# Micro_Conection.net
KiCad netlist of a schematic drawn in Altium Designer
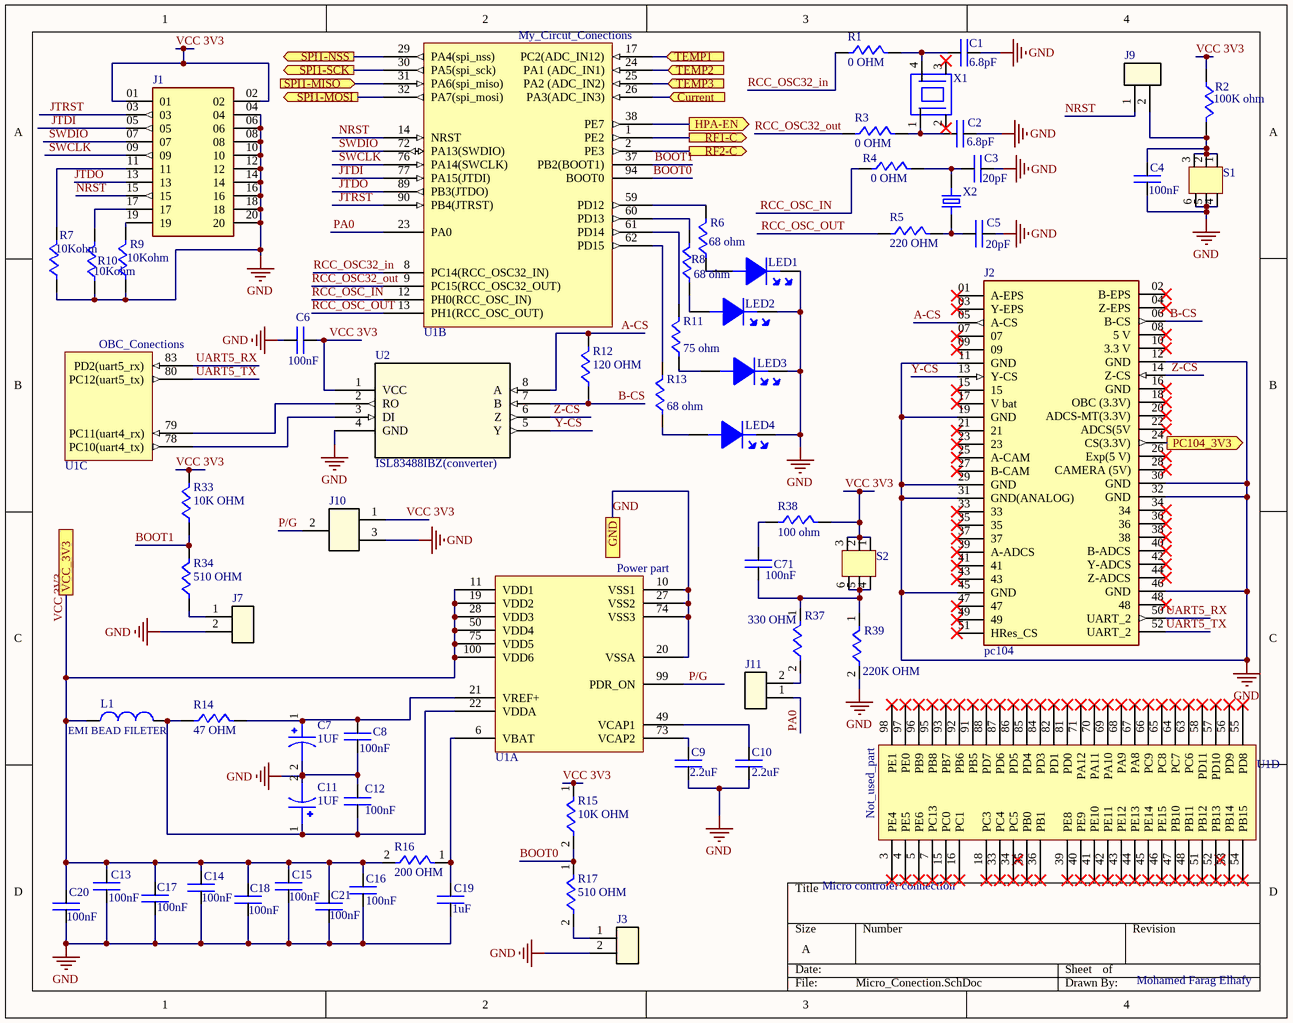
[diagram p0: Micro_Conection.SchDoc]

(export (version "E")
  (design (tool "Eeschema 10.0.6"))
  (components
    (comp (ref "C1")
      (value "CAP CER 6.8PF 100V NPO 0805")
      (footprint "0805 C")
      (description "6.8pF ±0.25pF 250V Ceramic Capacitor C0G, NP0 0805 (2012 Metric)")
      (fields
        (field (name "MANUFACTURER") "Yageo")
        (field (name "MANUFACTURER PART NUMBER") "CC0805CRNPO0BN6R8")
        (field (name "CAPACITANCE") "6.8pF")
      )
      (libsource (lib "comm sub") (part "C_6.8pF"))
    )
    (comp (ref "C2")
      (value "CAP CER 6.8PF 100V NPO 0805")
      (footprint "0805 C")
      (description "6.8pF ±0.25pF 250V Ceramic Capacitor C0G, NP0 0805 (2012 Metric)")
      (fields
        (field (name "MANUFACTURER") "Yageo")
        (field (name "MANUFACTURER PART NUMBER") "CC0805CRNPO0BN6R8")
        (field (name "CAPACITANCE") "6.8pF")
      )
      (libsource (lib "comm sub") (part "C_6.8pF"))
    )
    (comp (ref "C3")
      (value "CAP CER 20PF 25V NP0 0603")
      (footprint "0805 C")
      (description "20pF ±1% 25V Ceramic Capacitor C0G, NP0 0603 (1608 Metric)")
      (fields
        (field (name "MANUFACTURER") "Yageo")
        (field (name "MANUFACTURER PART NUMBER") "CC0805CRNPO0BN6R8")
        (field (name "CAPACITANCE") "20pF")
      )
      (libsource (lib "comm sub") (part "C_20pF"))
    )
    (comp (ref "C4")
      (value "CAP CER 0.1UF 10V 0805")
      (footprint "0805 C")
      (description "0.1µF ±10% 16V Ceramic Capacitor X7R 0805 (2012 Metric)")
      (fields
        (field (name "MANUFACTURER") "Johanson")
        (field (name "MANUFACTURER PART NUMBER") "160R15W104KV4T")
        (field (name "CAPACITANCE") "100nF")
      )
      (libsource (lib "comm sub") (part "C_100nF"))
    )
    (comp (ref "C5")
      (value "CAP CER 20PF 25V NP0 0603")
      (footprint "0805 C")
      (description "20pF ±1% 25V Ceramic Capacitor C0G, NP0 0603 (1608 Metric)")
      (fields
        (field (name "MANUFACTURER") "Yageo")
        (field (name "MANUFACTURER PART NUMBER") "CC0805CRNPO0BN6R8")
        (field (name "CAPACITANCE") "20pF")
      )
      (libsource (lib "comm sub") (part "C_20pF"))
    )
    (comp (ref "C6")
      (value "CAP CER 0.1UF 10V 0805")
      (footprint "0805 C")
      (description "0.1µF ±10% 16V Ceramic Capacitor X7R 0805 (2012 Metric)")
      (fields
        (field (name "MANUFACTURER") "Johanson")
        (field (name "MANUFACTURER PART NUMBER") "160R15W104KV4T")
        (field (name "CAPACITANCE") "100nF")
      )
      (libsource (lib "comm sub") (part "C_100nF"))
    )
    (comp (ref "C7")
      (value "1UF")
      (footprint "1206 C")
      (description "1µF Molded Tantalum Capacitors 16V 1206 (3216 Metric) 11Ohm")
      (libsource (lib "") (part "C_1uF 1206_1"))
    )
    (comp (ref "C8")
      (value "CAP CER 0.1UF 10V 0805")
      (footprint "0805 C")
      (description "0.1µF ±10% 16V Ceramic Capacitor X7R 0805 (2012 Metric)")
      (fields
        (field (name "MANUFACTURER") "Johanson")
        (field (name "MANUFACTURER PART NUMBER") "160R15W104KV4T")
        (field (name "CAPACITANCE") "100nF")
      )
      (libsource (lib "comm sub") (part "C_100nF"))
    )
    (comp (ref "C9")
      (value "CAP CER 2.2UF 25V X7R 0805")
      (footprint "0805 C")
      (description "2.2µF ±10% 25V Ceramic Capacitor X7R 0805 (2012 Metric)")
      (fields
        (field (name "MANUFACTURER") "Murata")
        (field (name "MANUFACTURER PART NUMBER") "GRM21BR71E225KE11L")
        (field (name "CAPACITANCE") "2.2uF")
      )
      (libsource (lib "comm sub") (part "C_2.2uF"))
    )
    (comp (ref "C10")
      (value "CAP CER 2.2UF 25V X7R 0805")
      (footprint "0805 C")
      (description "2.2µF ±10% 25V Ceramic Capacitor X7R 0805 (2012 Metric)")
      (fields
        (field (name "MANUFACTURER") "Murata")
        (field (name "MANUFACTURER PART NUMBER") "GRM21BR71E225KE11L")
        (field (name "CAPACITANCE") "2.2uF")
      )
      (libsource (lib "comm sub") (part "C_2.2uF"))
    )
    (comp (ref "C11")
      (value "1UF")
      (footprint "1206 C")
      (description "1µF Molded Tantalum Capacitors 16V 1206 (3216 Metric) 11Ohm")
      (libsource (lib "comm sub") (part "C_1uF 1206"))
    )
    (comp (ref "C12")
      (value "CAP CER 0.1UF 10V 0805")
      (footprint "0805 C")
      (description "0.1µF ±10% 16V Ceramic Capacitor X7R 0805 (2012 Metric)")
      (fields
        (field (name "MANUFACTURER") "Johanson")
        (field (name "MANUFACTURER PART NUMBER") "160R15W104KV4T")
        (field (name "CAPACITANCE") "100nF")
      )
      (libsource (lib "comm sub") (part "C_100nF"))
    )
    (comp (ref "C13")
      (value "CAP CER 0.1UF 10V 0805")
      (footprint "0805 C")
      (description "0.1µF ±10% 16V Ceramic Capacitor X7R 0805 (2012 Metric)")
      (fields
        (field (name "MANUFACTURER") "Johanson")
        (field (name "MANUFACTURER PART NUMBER") "160R15W104KV4T")
        (field (name "CAPACITANCE") "100nF")
      )
      (libsource (lib "comm sub") (part "C_100nF"))
    )
    (comp (ref "C14")
      (value "CAP CER 0.1UF 10V 0805")
      (footprint "0805 C")
      (description "0.1µF ±10% 16V Ceramic Capacitor X7R 0805 (2012 Metric)")
      (fields
        (field (name "MANUFACTURER") "Johanson")
        (field (name "MANUFACTURER PART NUMBER") "160R15W104KV4T")
        (field (name "CAPACITANCE") "100nF")
      )
      (libsource (lib "comm sub") (part "C_100nF"))
    )
    (comp (ref "C15")
      (value "CAP CER 0.1UF 10V 0805")
      (footprint "0805 C")
      (description "0.1µF ±10% 16V Ceramic Capacitor X7R 0805 (2012 Metric)")
      (fields
        (field (name "MANUFACTURER") "Johanson")
        (field (name "MANUFACTURER PART NUMBER") "160R15W104KV4T")
        (field (name "CAPACITANCE") "100nF")
      )
      (libsource (lib "comm sub") (part "C_100nF"))
    )
    (comp (ref "C16")
      (value "CAP CER 0.1UF 10V 0805")
      (footprint "0805 C")
      (description "0.1µF ±10% 16V Ceramic Capacitor X7R 0805 (2012 Metric)")
      (fields
        (field (name "MANUFACTURER") "Johanson")
        (field (name "MANUFACTURER PART NUMBER") "160R15W104KV4T")
        (field (name "CAPACITANCE") "100nF")
      )
      (libsource (lib "comm sub") (part "C_100nF"))
    )
    (comp (ref "C17")
      (value "CAP CER 0.1UF 10V 0805")
      (footprint "0805 C")
      (description "0.1µF ±10% 16V Ceramic Capacitor X7R 0805 (2012 Metric)")
      (fields
        (field (name "MANUFACTURER") "Johanson")
        (field (name "MANUFACTURER PART NUMBER") "160R15W104KV4T")
        (field (name "CAPACITANCE") "100nF")
      )
      (libsource (lib "comm sub") (part "C_100nF"))
    )
    (comp (ref "C18")
      (value "CAP CER 0.1UF 10V 0805")
      (footprint "0805 C")
      (description "0.1µF ±10% 16V Ceramic Capacitor X7R 0805 (2012 Metric)")
      (fields
        (field (name "MANUFACTURER") "Johanson")
        (field (name "MANUFACTURER PART NUMBER") "160R15W104KV4T")
        (field (name "CAPACITANCE") "100nF")
      )
      (libsource (lib "comm sub") (part "C_100nF"))
    )
    (comp (ref "C19")
      (value "CAP CER 1UF 16V X7R 0805")
      (footprint "0805 C")
      (description "1µF ±5% 16V Ceramic Capacitor X7R 0805 (2012 Metric)")
      (fields
        (field (name "MANUFACTURER") "Murata")
        (field (name "MANUFACTURER PART NUMBER") "GRM219R61H105KA73D")
        (field (name "CAPACITANCE") "1uF")
      )
      (libsource (lib "comm sub") (part "C_1uF"))
    )
    (comp (ref "C20")
      (value "CAP CER 0.1UF 10V 0805")
      (footprint "0805 C")
      (description "0.1µF ±10% 16V Ceramic Capacitor X7R 0805 (2012 Metric)")
      (fields
        (field (name "MANUFACTURER") "Johanson")
        (field (name "MANUFACTURER PART NUMBER") "160R15W104KV4T")
        (field (name "CAPACITANCE") "100nF")
      )
      (libsource (lib "comm sub") (part "C_100nF"))
    )
    (comp (ref "C21")
      (value "CAP CER 0.1UF 10V 0805")
      (footprint "0805 C")
      (description "0.1µF ±10% 16V Ceramic Capacitor X7R 0805 (2012 Metric)")
      (fields
        (field (name "MANUFACTURER") "Johanson")
        (field (name "MANUFACTURER PART NUMBER") "160R15W104KV4T")
        (field (name "CAPACITANCE") "100nF")
      )
      (libsource (lib "comm sub") (part "C_100nF"))
    )
    (comp (ref "C71")
      (value "CAP CER 0.1UF 10V 0805")
      (footprint "0805 C")
      (description "0.1µF ±10% 16V Ceramic Capacitor X7R 0805 (2012 Metric)")
      (fields
        (field (name "MANUFACTURER") "Johanson")
        (field (name "MANUFACTURER PART NUMBER") "160R15W104KV4T")
        (field (name "CAPACITANCE") "100nF")
      )
      (libsource (lib "Integrated_Library12-2-2021") (part "C_100nF"))
    )
    (comp (ref "J1")
      (value "CONN HEADER VERT 20POS 2.54MM")
      (footprint "JTAG")
      (description "Connector Header Through Hole 20 position 0.100\" (2.54mm)")
      (libsource (lib "comm sub") (part "JTAG"))
    )
    (comp (ref "J2")
      (value "pc104")
      (footprint "pc104")
      (libsource (lib "Integrated_Library1") (part "pc104"))
    )
    (comp (ref "J3")
      (value "CONN HEADER VERT 2POS 2.54MM")
      (footprint "jumber 2")
      (description "Connector Header Through Hole 2 position 0.100\" (2.54mm)")
      (fields
        (field (name "MANUFACTURER") "Wurth Electronics")
        (field (name "MANUFACTURER PART NUMBER") "61300211121")
      )
      (libsource (lib "") (part "jumber 2 leads_1"))
    )
    (comp (ref "J7")
      (value "CONN HEADER VERT 2POS 2.54MM")
      (footprint "jumber 2")
      (description "Connector Header Through Hole 2 position 0.100\" (2.54mm)")
      (fields
        (field (name "MANUFACTURER") "Wurth Electronics")
        (field (name "MANUFACTURER PART NUMBER") "61300211121")
      )
      (libsource (lib "") (part "jumber 2 leads_1"))
    )
    (comp (ref "J9")
      (value "CONN HEADER VERT 2POS 2.54MM")
      (footprint "jumber 2")
      (description "Connector Header Through Hole 2 position 0.100\" (2.54mm)")
      (fields
        (field (name "MANUFACTURER") "Wurth Electronics")
        (field (name "MANUFACTURER PART NUMBER") "61300211121")
      )
      (libsource (lib "") (part "jumber 2 leads_2"))
    )
    (comp (ref "J10")
      (value "CONN HEADER VERT 3POS 2.54MM")
      (footprint "jumber")
      (description "Connector Header Through Hole 3 position 0.100\" (2.54mm)")
      (fields (field (name "MANUFACTURER") "Harwin") (field (name "MANUFACTURER PART NUMBER") "M20-9990345"))
      (libsource (lib "Integrated_Library1") (part "jumber"))
    )
    (comp (ref "J11")
      (value "CONN HEADER VERT 2POS 2.54MM")
      (footprint "jumber 2")
      (description "Connector Header Through Hole 2 position 0.100\" (2.54mm)")
      (fields
        (field (name "MANUFACTURER") "Wurth Electronics")
        (field (name "MANUFACTURER PART NUMBER") "61300211121")
      )
      (libsource (lib "comm sub") (part "jumber 2 leads"))
    )
    (comp (ref "L1")
      (value "EMI BEAD FILETER")
      (footprint "0805 C")
      (description "60 Ohms @ 100MHz 1 Power Line Ferrite Bead 0805 (2012 Metric) 3A 25mOhm")
      (libsource (lib "comm sub") (part "FCM1608-0603"))
    )
    (comp (ref "LED1")
      (value "LED GREEN CLEAR CHIP SMD R/A")
      (footprint "LED")
      (description "Green 568nm LED Indication - Discrete 2V 0805 (2012 Metric)")
      (fields
        (field (name "MANUFACTURER") "Vishay Lite-On")
        (field (name "MANUFACTURER PART NUMBER") "LTST-S220KGKT")
      )
      (libsource (lib "comm sub") (part "LED_GREEN"))
    )
    (comp (ref "LED2")
      (value "LED ORANGE CLEAR SMD")
      (footprint "LED")
      (description "Orange 605nm LED Indication - Discrete 2V 0805 (2012 Metric)")
      (fields
        (field (name "MANUFACTURER") "Vishay Lite-On")
        (field (name "MANUFACTURER PART NUMBER") "LTST-C170KFKT")
      )
      (libsource (lib "comm sub") (part "LED_ORANGE"))
    )
    (comp (ref "LED3")
      (value "LED RED CLEAR SMD")
      (footprint "LED")
      (description "Red 638nm LED Indication - Discrete 1.8V 0805 (2012 Metric)")
      (fields
        (field (name "MANUFACTURER") "Vishay Lite-On")
        (field (name "MANUFACTURER PART NUMBER") "LTST-C170CKT")
      )
      (libsource (lib "comm sub") (part "LED_RED"))
    )
    (comp (ref "LED4")
      (value "LED YELLOW CLEAR SMD")
      (footprint "LED")
      (description "Yellow 591nm LED Indication - Discrete 2.1V 0805 (2012 Metric)")
      (fields
        (field (name "MANUFACTURER") "Vishay Lite-On")
        (field (name "MANUFACTURER PART NUMBER") "LTST-C170KSKT")
      )
      (libsource (lib "comm sub") (part "LED_YELLOW"))
    )
    (comp (ref "R1")
      (value "0 OHM")
      (footprint "0805 R")
      (description "0 Ohms Jumper 0.125W, 1/8W Chip Resistor 0805 (2012 Metric)  Thick Film")
      (fields
        (field (name "MANUFACTURER") "Vishay")
        (field (name "MANUFACTURER PART NUMBER") "CRCW08050000Z0EAC")
      )
      (libsource (lib "comm sub") (part "R_0 ohm"))
    )
    (comp (ref "R2")
      (value "100K ohm")
      (footprint "0805 R")
      (fields
        (field (name "MANUFACTURER") "Vishay")
        (field (name "MANUFACTURER PART NUMBER") "CRCW08050000Z0EAC")
        (field (name "TOLERANCE") "1%")
      )
      (libsource (lib "comm sub") (part "R_100k ohm"))
    )
    (comp (ref "R3")
      (value "0 OHM")
      (footprint "0805 R")
      (description "0 Ohms Jumper 0.125W, 1/8W Chip Resistor 0805 (2012 Metric)  Thick Film")
      (fields
        (field (name "MANUFACTURER") "Vishay")
        (field (name "MANUFACTURER PART NUMBER") "CRCW08050000Z0EAC")
      )
      (libsource (lib "comm sub") (part "R_0 ohm"))
    )
    (comp (ref "R4")
      (value "0 OHM")
      (footprint "0805 R")
      (description "0 Ohms Jumper 0.125W, 1/8W Chip Resistor 0805 (2012 Metric)  Thick Film")
      (fields
        (field (name "MANUFACTURER") "Vishay")
        (field (name "MANUFACTURER PART NUMBER") "CRCW08050000Z0EAC")
      )
      (libsource (lib "comm sub") (part "R_0 ohm"))
    )
    (comp (ref "R5")
      (value "220 OHM")
      (footprint "0805 R")
      (description "220 Ohms ±1% 0.125W, 1/8W Chip Resistor 0805 (2012 Metric) Automotive AEC-Q200 Thick Film")
      (fields
        (field (name "MANUFACTURER") "Panasonic")
        (field (name "MANUFACTURER PART NUMBER") "ERJ-P6WF2200V")
      )
      (libsource (lib "comm sub") (part "R_220 ohm"))
    )
    (comp (ref "R6")
      (value "RES 68 OHM 5% 1/4W 0805")
      (footprint "0805 R")
      (fields
        (field (name "MANUFACTURER") "Stackpole Electronics")
        (field (name "MANUFACTURER PART NUMBER") "RPC0805JT68R0")
        (field (name "TOLERANCE") "5%")
        (field (name "RESISTANCE") "68 ohm")
      )
      (libsource (lib "Integrated_Library12-2-2021") (part "R_68 ohm"))
    )
    (comp (ref "R7")
      (value "10Kohm")
      (footprint "0805 R")
      (fields
        (field (name "MANUFACTURER") "Panasonic")
        (field (name "MANUFACTURER PART NUMBER") "ERJP6WF1002V")
        (field (name "TOLERANCE") "1%")
      )
      (libsource (lib "") (part "R_10 k_1"))
    )
    (comp (ref "R8")
      (value "RES 68 OHM 5% 1/4W 0805")
      (footprint "0805 R")
      (fields
        (field (name "MANUFACTURER") "Stackpole Electronics")
        (field (name "MANUFACTURER PART NUMBER") "RPC0805JT68R0")
        (field (name "TOLERANCE") "5%")
        (field (name "RESISTANCE") "68 ohm")
      )
      (libsource (lib "Integrated_Library12-2-2021") (part "R_68 ohm"))
    )
    (comp (ref "R9")
      (value "10Kohm")
      (footprint "0805 R")
      (fields
        (field (name "MANUFACTURER") "Panasonic")
        (field (name "MANUFACTURER PART NUMBER") "ERJP6WF1002V")
        (field (name "TOLERANCE") "1%")
      )
      (libsource (lib "") (part "R_10 k_1"))
    )
    (comp (ref "R10")
      (value "10Kohm")
      (footprint "0805 R")
      (fields
        (field (name "MANUFACTURER") "Panasonic")
        (field (name "MANUFACTURER PART NUMBER") "ERJP6WF1002V")
        (field (name "TOLERANCE") "1%")
      )
      (libsource (lib "") (part "R_10 k_1"))
    )
    (comp (ref "R11")
      (value "RES 75 OHM 1% 1/4W 0805")
      (footprint "0805 R")
      (description "75 Ohms ±1% 0.25W, 1/4W Chip Resistor 0805 (2012 Metric) Anti-Sulfur, Moisture Resistant Thin Film")
      (fields
        (field (name "MANUFACTURER") "Stackpole Electronics")
        (field (name "MANUFACTURER PART NUMBER") "RNCP0805FTD75R0")
        (field (name "RESISTANCE") "75 ohm")
      )
      (libsource (lib "Integrated_Library12-2-2021") (part "R_75 ohm"))
    )
    (comp (ref "R12")
      (value "120 OHM")
      (footprint "0805 R")
      (fields
        (field (name "MANUFACTURER") "Panasonic")
        (field (name "MANUFACTURER PART NUMBER") "ERJ-P06J121V")
        (field (name "TOLERANCE") "5%")
      )
      (libsource (lib "comm sub") (part "R_120 ohm"))
    )
    (comp (ref "R13")
      (value "RES 68 OHM 5% 1/4W 0805")
      (footprint "0805 R")
      (fields
        (field (name "MANUFACTURER") "Stackpole Electronics")
        (field (name "MANUFACTURER PART NUMBER") "RPC0805JT68R0")
        (field (name "TOLERANCE") "5%")
        (field (name "RESISTANCE") "68 ohm")
      )
      (libsource (lib "Integrated_Library12-2-2021") (part "R_68 ohm"))
    )
    (comp (ref "R14")
      (value "47 OHM")
      (footprint "0805 R")
      (fields
        (field (name "MANUFACTURER") "Panasonic")
        (field (name "MANUFACTURER PART NUMBER") "ERJ-P6WF47R0V")
        (field (name "TOLERANCE") "1%")
      )
      (libsource (lib "comm sub") (part "R_47 ohm"))
    )
    (comp (ref "R15")
      (value "10K OHM")
      (footprint "0805 R")
      (fields
        (field (name "MANUFACTURER") "Panasonic")
        (field (name "MANUFACTURER PART NUMBER") "ERJP6WF1002V")
        (field (name "TOLERANCE") "1%")
      )
      (libsource (lib "comm sub") (part "R_10 k"))
    )
    (comp (ref "R16")
      (value "200 OHM")
      (footprint "0805 R")
      (description "200 Ohms ±0.1% 0.125W, 1/8W Chip Resistor 0805 (2012 Metric) Automotive AEC-Q200 Thin Film")
      (fields
        (field (name "MANUFACTURER") "Panasonic")
        (field (name "MANUFACTURER PART NUMBER") "ERJ-P06F2000V")
      )
      (libsource (lib "comm sub") (part "R_200 ohm"))
    )
    (comp (ref "R17")
      (value "510 OHM")
      (footprint "0805 R")
      (description "510 Ohms ±1% 0.125W, 1/8W Chip Resistor 0805 (2012 Metric)  Thick Film")
      (fields
        (field (name "MANUFACTURER") "Panasonic")
        (field (name "MANUFACTURER PART NUMBER") "ERJ-6ENF5100V")
      )
      (libsource (lib "") (part "R_510ohm_1"))
    )
    (comp (ref "R33")
      (value "10K OHM")
      (footprint "0805 R")
      (fields
        (field (name "MANUFACTURER") "Panasonic")
        (field (name "MANUFACTURER PART NUMBER") "ERJP6WF1002V")
        (field (name "TOLERANCE") "1%")
      )
      (libsource (lib "") (part "R_10 k_1"))
    )
    (comp (ref "R34")
      (value "510 OHM")
      (footprint "0805 R")
      (description "510 Ohms ±1% 0.125W, 1/8W Chip Resistor 0805 (2012 Metric)  Thick Film")
      (fields
        (field (name "MANUFACTURER") "Panasonic")
        (field (name "MANUFACTURER PART NUMBER") "ERJ-6ENF5100V")
      )
      (libsource (lib "comm sub") (part "R_510ohm"))
    )
    (comp (ref "R37")
      (value "330 OHM")
      (footprint "0805 R")
      (fields
        (field (name "MANUFACTURER") "Panasonic")
        (field (name "MANUFACTURER PART NUMBER") "ERJ-6ENF3300V")
        (field (name "TOLERANCE") "1%")
      )
      (libsource (lib "Integrated_Library12-2-2021") (part "R_330 ohm"))
    )
    (comp (ref "R38")
      (value "RES SMD 100 OHM 5% 1/2W 0805")
      (footprint "0805 R")
      (fields
        (field (name "MANUFACTURER") "Panasonic")
        (field (name "MANUFACTURER PART NUMBER") "ERJ-P06J101V")
        (field (name "TOLERANCE") "5%")
        (field (name "RESISTANCE") "100 ohm")
      )
      (libsource (lib "Integrated_Library12-2-2021") (part "R_100 ohm"))
    )
    (comp (ref "R39")
      (value "220K OHM")
      (footprint "0805 R")
      (fields
        (field (name "MANUFACTURER") "Vishay")
        (field (name "MANUFACTURER PART NUMBER") "CRCW0805220KFKEAC")
        (field (name "TOLERANCE") "5%")
      )
      (libsource (lib "Integrated_Library12-2-2021") (part "R_220 k"))
    )
    (comp (ref "S1")
      (value "Pushbutton Switches 2 Poles Vertical")
      (footprint "push button")
      (description "Pushbutton Switches 2 Poles Vertical .2A 14V 1.7mm Travel")
      (fields
        (field (name "MANUFACTURER") "Alps Electric")
        (field (name "MANUFACTURER PART NUMBER") "SPEJ110100")
      )
      (libsource (lib "Integrated_Library12-2-2021") (part "push button"))
    )
    (comp (ref "S2")
      (value "Pushbutton Switches 2 Poles Vertical")
      (footprint "push button")
      (description "Pushbutton Switches 2 Poles Vertical .2A 14V 1.7mm Travel")
      (fields
        (field (name "MANUFACTURER") "Alps Electric")
        (field (name "MANUFACTURER PART NUMBER") "SPEJ110100")
      )
      (libsource (lib "Integrated_Library12-2-2021") (part "push button"))
    )
    (comp (ref "U1")
      (value "STM32F407VGT6_1")
      (footprint "STM32F407VGT6 P")
      (description "ARM® Cortex®-M4 STM32F4 Microcontroller IC 32-Bit 168MHz 1MB (1M x 8) FLASH 100-LQFP (14x14)")
      (libsource (lib "STMLib") (part "STM32F407VGT6_1"))
    )
    (comp (ref "U2")
      (value "ISL83488IBZ(converter)")
      (footprint "ISL83488IBZ")
      (libsource (lib "Integrated_Library1") (part "ISL83488IBZ(converter)"))
    )
    (comp (ref "X1")
      (value "MC-146 32.7680KA-E3: ROHS")
      (footprint "CRYSTAL 32K")
      (description "32.768kHz ±20ppm Crystal 6pF 65 kOhm -40°C ~ 85°C  Surface Mount 4-SMD, J-Lead")
      (fields (field (name "MANUFACTURER") "Epson"))
      (libsource (lib "Integrated_Library1") (part "MC-146 32.7680KA-E3{colon} ROHS"))
    )
    (comp (ref "X2")
      (value "CRYSTAL 8.0000MHZ 32PF SMD")
      (footprint "XTAL_ECS-80-32-5PX-TR")
      (description "8MHz Â±30ppm Crystal 32pF 60 Ohms HC-49/US")
      (fields (field (name "MF") "ECS Inc.") (field (name "DIGI-KEY_PART_NUMBER") "XC1272CT-ND"))
      (libsource (lib "comm sub") (part "ECS-80-32-5PX-TR"))
    )
  )
  (nets
    (net (code "1") (name "/A-CS") (class "Default")
      (node (ref "J2") (pin "05") (pinfunction "A-CS_05") (pintype "output"))
      (node (ref "R12") (pin "1") (pinfunction "1_1") (pintype "passive"))
      (node (ref "U2") (pin "8") (pinfunction "A_8") (pintype "input"))
    )
    (net (code "2") (name "/B-CS") (class "Default")
      (node (ref "J2") (pin "06") (pinfunction "B-CS_06") (pintype "output"))
      (node (ref "R12") (pin "2") (pinfunction "2_2") (pintype "passive"))
      (node (ref "U2") (pin "7") (pinfunction "B_7") (pintype "input"))
    )
    (net (code "3") (name "/BOOT0") (class "Default")
      (node (ref "R15") (pin "2") (pinfunction "2_2") (pintype "passive"))
      (node (ref "R17") (pin "1") (pinfunction "1_1") (pintype "passive"))
      (node (ref "U1") (pin "94") (pinfunction "BOOT0_94") (pintype "passive"))
    )
    (net (code "4") (name "/BOOT1") (class "Default")
      (node (ref "R33") (pin "2") (pinfunction "2_2") (pintype "passive"))
      (node (ref "R34") (pin "1") (pinfunction "1_1") (pintype "passive"))
      (node (ref "U1") (pin "37") (pinfunction "PB2(BOOT1)_37") (pintype "passive"))
    )
    (net (code "5") (name "/Current") (class "Default")
      (node (ref "U1") (pin "26") (pinfunction "PA3(ADC_IN3)_26") (pintype "input"))
    )
    (net (code "6") (name "/HPA-EN") (class "Default")
      (node (ref "U1") (pin "38") (pinfunction "PE7_38") (pintype "output"))
    )
    (net (code "7") (name "/JTDI") (class "Default")
      (node (ref "J1") (pin "05") (pinfunction "05_05") (pintype "output"))
      (node (ref "U1") (pin "77") (pinfunction "PA15(JTDI)_77") (pintype "input"))
    )
    (net (code "8") (name "/JTDO") (class "Default")
      (node (ref "J1") (pin "13") (pinfunction "13_13") (pintype "passive"))
      (node (ref "U1") (pin "89") (pinfunction "PB3(JTDO)_89") (pintype "output"))
    )
    (net (code "9") (name "/JTRST") (class "Default")
      (node (ref "J1") (pin "03") (pinfunction "03_03") (pintype "output"))
      (node (ref "U1") (pin "90") (pinfunction "PB4(JTRST)_90") (pintype "input"))
    )
    (net (code "10") (name "/NRST") (class "Default")
      (node (ref "J1") (pin "15") (pinfunction "15_15") (pintype "output"))
      (node (ref "J9") (pin "1") (pinfunction "1_1") (pintype "passive"))
      (node (ref "U1") (pin "14") (pinfunction "NRST_14") (pintype "input"))
    )
    (net (code "11") (name "/PA0") (class "Default")
      (node (ref "J11") (pin "1") (pinfunction "1_1") (pintype "passive"))
      (node (ref "U1") (pin "23") (pinfunction "PA0_23") (pintype "power_in"))
    )
    (net (code "12") (name "/PC104_3V3") (class "Default")
      (node (ref "J2") (pin "24") (pinfunction "CS(3.3V)_24") (pintype "output"))
    )
    (net (code "13") (name "/P{slash}G") (class "Default")
      (node (ref "J10") (pin "2") (pinfunction "2_2") (pintype "passive"))
      (node (ref "U1") (pin "99") (pinfunction "PDR_ON_99") (pintype "power_in"))
    )
    (net (code "14") (name "/RCC_OSC32_in") (class "Default")
      (node (ref "R1") (pin "2") (pinfunction "2_2") (pintype "passive"))
      (node (ref "U1") (pin "8") (pinfunction "PC14(RCC_OSC32_IN)_8") (pintype "passive"))
    )
    (net (code "15") (name "/RCC_OSC32_out") (class "Default")
      (node (ref "R3") (pin "2") (pinfunction "2_2") (pintype "passive"))
      (node (ref "U1") (pin "9") (pinfunction "PC15(RCC_OSC32_OUT)_9") (pintype "passive"))
    )
    (net (code "16") (name "/RCC_OSC_IN") (class "Default")
      (node (ref "R4") (pin "2") (pinfunction "2_2") (pintype "passive"))
      (node (ref "U1") (pin "12") (pinfunction "PH0(RCC_OSC_IN)_12") (pintype "passive"))
    )
    (net (code "17") (name "/RCC_OSC_OUT") (class "Default")
      (node (ref "R5") (pin "2") (pinfunction "2_2") (pintype "passive"))
      (node (ref "U1") (pin "13") (pinfunction "PH1(RCC_OSC_OUT)_13") (pintype "passive"))
    )
    (net (code "18") (name "/RF1-C") (class "Default")
      (node (ref "U1") (pin "1") (pinfunction "PE2_1") (pintype "output"))
    )
    (net (code "19") (name "/RF2-C") (class "Default")
      (node (ref "U1") (pin "2") (pinfunction "PE3_2") (pintype "output"))
    )
    (net (code "20") (name "/SPI1-MISO") (class "Default")
      (node (ref "U1") (pin "31") (pinfunction "PA6(spi_miso)_31") (pintype "input"))
    )
    (net (code "21") (name "/SPI1-MOSI") (class "Default")
      (node (ref "U1") (pin "32") (pinfunction "PA7(spi_mosi)_32") (pintype "output"))
    )
    (net (code "22") (name "/SPI1-NSS") (class "Default")
      (node (ref "U1") (pin "29") (pinfunction "PA4(spi_nss)_29") (pintype "output"))
    )
    (net (code "23") (name "/SPI1-SCK") (class "Default")
      (node (ref "U1") (pin "30") (pinfunction "PA5(spi_sck)_30") (pintype "output"))
    )
    (net (code "24") (name "/SWCLK") (class "Default")
      (node (ref "J1") (pin "09") (pinfunction "09_09") (pintype "output"))
      (node (ref "U1") (pin "76") (pinfunction "PA14(SWCLK)_76") (pintype "input"))
    )
    (net (code "25") (name "/SWDIO") (class "Default")
      (node (ref "J1") (pin "07") (pinfunction "07_07") (pintype "passive"))
      (node (ref "U1") (pin "72") (pinfunction "PA13(SWDIO)_72") (pintype "bidirectional"))
    )
    (net (code "26") (name "/TEMP1") (class "Default")
      (node (ref "U1") (pin "17") (pinfunction "PC2(ADC_IN12)_17") (pintype "input"))
    )
    (net (code "27") (name "/TEMP2") (class "Default")
      (node (ref "U1") (pin "24") (pinfunction "PA1_(ADC_IN1)_24") (pintype "input"))
    )
    (net (code "28") (name "/TEMP3") (class "Default")
      (node (ref "U1") (pin "25") (pinfunction "PA2_(ADC_IN2)_25") (pintype "input"))
    )
    (net (code "29") (name "/UART5_RX") (class "Default")
      (node (ref "J2") (pin "50") (pinfunction "UART_2_50") (pintype "output"))
      (node (ref "U1") (pin "83") (pinfunction "PD2(uart5_rx)_83") (pintype "input"))
    )
    (net (code "30") (name "/UART5_TX") (class "Default")
      (node (ref "J2") (pin "52") (pinfunction "UART_2_52") (pintype "passive"))
      (node (ref "U1") (pin "80") (pinfunction "PC12(uart5_tx)_80") (pintype "output"))
    )
    (net (code "31") (name "/VCC 3V3") (class "Default")
      (node (ref "C13") (pin "1") (pinfunction "1_1") (pintype "passive"))
      (node (ref "C14") (pin "1") (pinfunction "1_1") (pintype "passive"))
      (node (ref "C15") (pin "1") (pinfunction "1_1") (pintype "passive"))
      (node (ref "C16") (pin "1") (pinfunction "1_1") (pintype "passive"))
      (node (ref "C17") (pin "1") (pinfunction "1_1") (pintype "passive"))
      (node (ref "C18") (pin "1") (pinfunction "1_1") (pintype "passive"))
      (node (ref "C20") (pin "1") (pinfunction "1_1") (pintype "passive"))
      (node (ref "C21") (pin "1") (pinfunction "1_1") (pintype "passive"))
      (node (ref "C6") (pin "2") (pinfunction "2_2") (pintype "passive"))
      (node (ref "J1") (pin "01") (pinfunction "01_01") (pintype "passive"))
      (node (ref "J1") (pin "02") (pinfunction "02_02") (pintype "passive"))
      (node (ref "J10") (pin "1") (pinfunction "1_1") (pintype "passive"))
      (node (ref "L1") (pin "2") (pinfunction "2_2") (pintype "passive"))
      (node (ref "R15") (pin "1") (pinfunction "1_1") (pintype "passive"))
      (node (ref "R16") (pin "2") (pinfunction "2_2") (pintype "passive"))
      (node (ref "R2") (pin "2") (pinfunction "2_2") (pintype "passive"))
      (node (ref "R33") (pin "1") (pinfunction "1_1") (pintype "passive"))
      (node (ref "R38") (pin "1") (pinfunction "1_1") (pintype "passive"))
      (node (ref "S2") (pin "1") (pinfunction "1_1") (pintype "passive"))
      (node (ref "S2") (pin "2") (pinfunction "2_2") (pintype "passive"))
      (node (ref "S2") (pin "3") (pinfunction "3_3") (pintype "passive"))
      (node (ref "U1") (pin "100") (pinfunction "VDD6_100") (pintype "power_in"))
      (node (ref "U1") (pin "11") (pinfunction "VDD1_11") (pintype "power_in"))
      (node (ref "U1") (pin "19") (pinfunction "VDD2_19") (pintype "power_in"))
      (node (ref "U1") (pin "28") (pinfunction "VDD3_28") (pintype "power_in"))
      (node (ref "U1") (pin "50") (pinfunction "VDD4_50") (pintype "power_in"))
      (node (ref "U1") (pin "75") (pinfunction "VDD5_75") (pintype "power_in"))
      (node (ref "U2") (pin "1") (pinfunction "VCC_1") (pintype "power_in"))
    )
    (net (code "32") (name "/Y-CS") (class "Default")
      (node (ref "J2") (pin "13") (pinfunction "Y-CS_13") (pintype "input"))
      (node (ref "U2") (pin "5") (pinfunction "Y_5") (pintype "output"))
    )
    (net (code "33") (name "/Z-CS") (class "Default")
      (node (ref "J2") (pin "14") (pinfunction "Z-CS_14") (pintype "input"))
      (node (ref "U2") (pin "6") (pinfunction "Z_6") (pintype "output"))
    )
    (net (code "34") (name "GND") (class "Default")
      (node (ref "C1") (pin "1") (pinfunction "1_1") (pintype "passive"))
      (node (ref "C10") (pin "2") (pinfunction "2_2") (pintype "passive"))
      (node (ref "C11") (pin "2") (pinfunction "2_2") (pintype "passive"))
      (node (ref "C12") (pin "1") (pinfunction "1_1") (pintype "passive"))
      (node (ref "C13") (pin "2") (pinfunction "2_2") (pintype "passive"))
      (node (ref "C14") (pin "2") (pinfunction "2_2") (pintype "passive"))
      (node (ref "C15") (pin "2") (pinfunction "2_2") (pintype "passive"))
      (node (ref "C16") (pin "2") (pinfunction "2_2") (pintype "passive"))
      (node (ref "C17") (pin "2") (pinfunction "2_2") (pintype "passive"))
      (node (ref "C18") (pin "2") (pinfunction "2_2") (pintype "passive"))
      (node (ref "C19") (pin "2") (pinfunction "2_2") (pintype "passive"))
      (node (ref "C2") (pin "1") (pinfunction "1_1") (pintype "passive"))
      (node (ref "C20") (pin "2") (pinfunction "2_2") (pintype "passive"))
      (node (ref "C21") (pin "2") (pinfunction "2_2") (pintype "passive"))
      (node (ref "C3") (pin "1") (pinfunction "1_1") (pintype "passive"))
      (node (ref "C4") (pin "2") (pinfunction "2_2") (pintype "passive"))
      (node (ref "C5") (pin "1") (pinfunction "1_1") (pintype "passive"))
      (node (ref "C6") (pin "1") (pinfunction "1_1") (pintype "passive"))
      (node (ref "C7") (pin "2") (pinfunction "2_2") (pintype "passive"))
      (node (ref "C8") (pin "2") (pinfunction "2_2") (pintype "passive"))
      (node (ref "C9") (pin "2") (pinfunction "2_2") (pintype "passive"))
      (node (ref "J1") (pin "04") (pinfunction "04_04") (pintype "passive"))
      (node (ref "J1") (pin "06") (pinfunction "06_06") (pintype "passive"))
      (node (ref "J1") (pin "08") (pinfunction "08_08") (pintype "passive"))
      (node (ref "J1") (pin "10") (pinfunction "10_10") (pintype "passive"))
      (node (ref "J1") (pin "12") (pinfunction "12_12") (pintype "passive"))
      (node (ref "J1") (pin "14") (pinfunction "14_14") (pintype "passive"))
      (node (ref "J1") (pin "16") (pinfunction "16_16") (pintype "passive"))
      (node (ref "J1") (pin "18") (pinfunction "18_18") (pintype "passive"))
      (node (ref "J1") (pin "20") (pinfunction "20_20") (pintype "passive"))
      (node (ref "J10") (pin "3") (pinfunction "3_3") (pintype "passive"))
      (node (ref "J2") (pin "11") (pinfunction "GND_11") (pintype "passive"))
      (node (ref "J2") (pin "12") (pinfunction "GND_12") (pintype "passive"))
      (node (ref "J2") (pin "19") (pinfunction "GND_19") (pintype "passive"))
      (node (ref "J2") (pin "29") (pinfunction "GND_29") (pintype "passive"))
      (node (ref "J2") (pin "30") (pinfunction "GND_30") (pintype "passive"))
      (node (ref "J2") (pin "31") (pinfunction "GND(ANALOG)_31") (pintype "passive"))
      (node (ref "J2") (pin "32") (pinfunction "GND_32") (pintype "passive"))
      (node (ref "J2") (pin "45") (pinfunction "GND_45") (pintype "passive"))
      (node (ref "J2") (pin "46") (pinfunction "GND_46") (pintype "passive"))
      (node (ref "J3") (pin "2") (pinfunction "2_2") (pintype "passive"))
      (node (ref "J7") (pin "2") (pinfunction "2_2") (pintype "passive"))
      (node (ref "LED1") (pin "2") (pinfunction "2_2") (pintype "passive"))
      (node (ref "LED2") (pin "2") (pinfunction "2_2") (pintype "passive"))
      (node (ref "LED3") (pin "2") (pinfunction "2_2") (pintype "passive"))
      (node (ref "LED4") (pin "2") (pinfunction "2_2") (pintype "passive"))
      (node (ref "R10") (pin "2") (pinfunction "2_2") (pintype "passive"))
      (node (ref "R39") (pin "2") (pinfunction "2_2") (pintype "passive"))
      (node (ref "R7") (pin "2") (pinfunction "2_2") (pintype "passive"))
      (node (ref "R9") (pin "2") (pinfunction "2_2") (pintype "passive"))
      (node (ref "S1") (pin "4") (pinfunction "4_4") (pintype "passive"))
      (node (ref "S1") (pin "5") (pinfunction "5_5") (pintype "passive"))
      (node (ref "S1") (pin "6") (pinfunction "6_6") (pintype "passive"))
      (node (ref "U1") (pin "10") (pinfunction "VSS1_10") (pintype "power_in"))
      (node (ref "U1") (pin "20") (pinfunction "VSSA_20") (pintype "power_in"))
      (node (ref "U1") (pin "27") (pinfunction "VSS2_27") (pintype "power_in"))
      (node (ref "U1") (pin "74") (pinfunction "VSS3_74") (pintype "power_in"))
      (node (ref "U2") (pin "4") (pinfunction "GND_4") (pintype "power_in"))
    )
    (net (code "35") (name "Net-(C2-Pad2)") (class "Default")
      (node (ref "C2") (pin "2") (pinfunction "2_2") (pintype "passive"))
      (node (ref "R3") (pin "1") (pinfunction "1_1") (pintype "passive"))
      (node (ref "X1") (pin "1") (pinfunction "1_1") (pintype "passive"))
    )
    (net (code "36") (name "Net-(C3-Pad2)") (class "Default")
      (node (ref "C3") (pin "2") (pinfunction "2_2") (pintype "passive"))
      (node (ref "R4") (pin "1") (pinfunction "1_1") (pintype "passive"))
      (node (ref "X2") (pin "2") (pinfunction "2_2") (pintype "passive"))
    )
    (net (code "37") (name "Net-(C4-Pad1)") (class "Default")
      (node (ref "C4") (pin "1") (pinfunction "1_1") (pintype "passive"))
      (node (ref "J9") (pin "2") (pinfunction "2_2") (pintype "passive"))
      (node (ref "R2") (pin "1") (pinfunction "1_1") (pintype "passive"))
      (node (ref "S1") (pin "1") (pinfunction "1_1") (pintype "passive"))
      (node (ref "S1") (pin "2") (pinfunction "2_2") (pintype "passive"))
      (node (ref "S1") (pin "3") (pinfunction "3_3") (pintype "passive"))
    )
    (net (code "38") (name "Net-(C5-Pad2)") (class "Default")
      (node (ref "C5") (pin "2") (pinfunction "2_2") (pintype "passive"))
      (node (ref "R5") (pin "1") (pinfunction "1_1") (pintype "passive"))
      (node (ref "X2") (pin "1") (pinfunction "1_1") (pintype "passive"))
    )
    (net (code "39") (name "Net-(C71-Pad1)") (class "Default")
      (node (ref "C71") (pin "1") (pinfunction "1_1") (pintype "passive"))
      (node (ref "R38") (pin "2") (pinfunction "2_2") (pintype "passive"))
    )
    (net (code "40") (name "Net-(C71-Pad2)") (class "Default")
      (node (ref "C71") (pin "2") (pinfunction "2_2") (pintype "passive"))
      (node (ref "R37") (pin "1") (pinfunction "1_1") (pintype "passive"))
      (node (ref "R39") (pin "1") (pinfunction "1_1") (pintype "passive"))
      (node (ref "S2") (pin "4") (pinfunction "4_4") (pintype "passive"))
      (node (ref "S2") (pin "5") (pinfunction "5_5") (pintype "passive"))
      (node (ref "S2") (pin "6") (pinfunction "6_6") (pintype "passive"))
    )
    (net (code "41") (name "Net-(J1-Pad11)") (class "Default")
      (node (ref "J1") (pin "11") (pinfunction "11_11") (pintype "passive"))
      (node (ref "R7") (pin "1") (pinfunction "1_1") (pintype "passive"))
    )
    (net (code "42") (name "Net-(J1-Pad17)") (class "Default")
      (node (ref "J1") (pin "17") (pinfunction "17_17") (pintype "passive"))
      (node (ref "R10") (pin "1") (pinfunction "1_1") (pintype "passive"))
    )
    (net (code "43") (name "Net-(J1-Pad19)") (class "Default")
      (node (ref "J1") (pin "19") (pinfunction "19_19") (pintype "passive"))
      (node (ref "R9") (pin "1") (pinfunction "1_1") (pintype "passive"))
    )
    (net (code "44") (name "Net-(J3-Pad1)") (class "Default")
      (node (ref "J3") (pin "1") (pinfunction "1_1") (pintype "passive"))
      (node (ref "R17") (pin "2") (pinfunction "2_2") (pintype "passive"))
    )
    (net (code "45") (name "Net-(J7-Pad1)") (class "Default")
      (node (ref "J7") (pin "1") (pinfunction "1_1") (pintype "passive"))
      (node (ref "R34") (pin "2") (pinfunction "2_2") (pintype "passive"))
    )
    (net (code "46") (name "Net-(J11-Pad2)") (class "Default")
      (node (ref "J11") (pin "2") (pinfunction "2_2") (pintype "passive"))
      (node (ref "R37") (pin "2") (pinfunction "2_2") (pintype "passive"))
    )
    (net (code "47") (name "Net-(LED1-Pad1)") (class "Default")
      (node (ref "LED1") (pin "1") (pinfunction "1_1") (pintype "passive"))
      (node (ref "R6") (pin "2") (pinfunction "2_2") (pintype "passive"))
    )
    (net (code "48") (name "Net-(LED2-Pad1)") (class "Default")
      (node (ref "LED2") (pin "1") (pinfunction "1_1") (pintype "passive"))
      (node (ref "R8") (pin "2") (pinfunction "2_2") (pintype "passive"))
    )
    (net (code "49") (name "Net-(LED3-Pad1)") (class "Default")
      (node (ref "LED3") (pin "1") (pinfunction "1_1") (pintype "passive"))
      (node (ref "R11") (pin "2") (pinfunction "2_2") (pintype "passive"))
    )
    (net (code "50") (name "Net-(LED4-Pad1)") (class "Default")
      (node (ref "LED4") (pin "1") (pinfunction "1_1") (pintype "passive"))
      (node (ref "R13") (pin "2") (pinfunction "2_2") (pintype "passive"))
    )
    (net (code "51") (name "Net-(U1A-VBAT)") (class "Default")
      (node (ref "C19") (pin "1") (pinfunction "1_1") (pintype "passive"))
      (node (ref "R16") (pin "1") (pinfunction "1_1") (pintype "passive"))
      (node (ref "U1") (pin "6") (pinfunction "VBAT_6") (pintype "power_in"))
    )
    (net (code "52") (name "Net-(U1A-VCAP1)") (class "Default")
      (node (ref "C10") (pin "1") (pinfunction "1_1") (pintype "passive"))
      (node (ref "U1") (pin "49") (pinfunction "VCAP1_49") (pintype "power_in"))
    )
    (net (code "53") (name "Net-(U1A-VCAP2)") (class "Default")
      (node (ref "C9") (pin "1") (pinfunction "1_1") (pintype "passive"))
      (node (ref "U1") (pin "73") (pinfunction "VCAP2_73") (pintype "power_in"))
    )
    (net (code "54") (name "Net-(U1A-VDDA)") (class "Default")
      (node (ref "C11") (pin "1") (pinfunction "1_1") (pintype "passive"))
      (node (ref "C12") (pin "2") (pinfunction "2_2") (pintype "passive"))
      (node (ref "L1") (pin "1") (pintype "passive"))
      (node (ref "R14") (pin "2") (pinfunction "2_2") (pintype "passive"))
      (node (ref "U1") (pin "22") (pinfunction "VDDA_22") (pintype "power_in"))
    )
    (net (code "55") (name "Net-(U1A-VREF+)") (class "Default")
      (node (ref "C7") (pin "1") (pinfunction "1_1") (pintype "passive"))
      (node (ref "C8") (pin "1") (pinfunction "1_1") (pintype "passive"))
      (node (ref "R14") (pin "1") (pinfunction "1_1") (pintype "passive"))
      (node (ref "U1") (pin "21") (pinfunction "VREF+_21") (pintype "power_in"))
    )
    (net (code "56") (name "Net-(U1B-PD12)") (class "Default")
      (node (ref "R6") (pin "1") (pinfunction "1_1") (pintype "passive"))
      (node (ref "U1") (pin "59") (pinfunction "PD12_59") (pintype "output"))
    )
    (net (code "57") (name "Net-(U1B-PD13)") (class "Default")
      (node (ref "R8") (pin "1") (pinfunction "1_1") (pintype "passive"))
      (node (ref "U1") (pin "60") (pinfunction "PD13_60") (pintype "output"))
    )
    (net (code "58") (name "Net-(U1B-PD14)") (class "Default")
      (node (ref "R11") (pin "1") (pinfunction "1_1") (pintype "passive"))
      (node (ref "U1") (pin "61") (pinfunction "PD14_61") (pintype "output"))
    )
    (net (code "59") (name "Net-(U1B-PD15)") (class "Default")
      (node (ref "R13") (pin "1") (pinfunction "1_1") (pintype "passive"))
      (node (ref "U1") (pin "62") (pinfunction "PD15_62") (pintype "output"))
    )
    (net (code "60") (name "Net-(U1C-PC10(uart4_tx))") (class "Default")
      (node (ref "U1") (pin "78") (pinfunction "PC10(uart4_tx)_78") (pintype "output"))
      (node (ref "U2") (pin "3") (pinfunction "DI_3") (pintype "input"))
    )
    (net (code "61") (name "Net-(U1C-PC11(uart4_rx))") (class "Default")
      (node (ref "U1") (pin "79") (pinfunction "PC11(uart4_rx)_79") (pintype "input"))
      (node (ref "U2") (pin "2") (pinfunction "RO_2") (pintype "output"))
    )
    (net (code "62") (name "Net-(X1-3)") (class "Default")
      (node (ref "C1") (pin "2") (pinfunction "2_2") (pintype "passive"))
      (node (ref "R1") (pin "1") (pinfunction "1_1") (pintype "passive"))
      (node (ref "X1") (pin "4") (pinfunction "3_4") (pintype "passive"))
    )
    (net (code "63") (name "unconnected-(J2-3.3_V-Pad10)") (class "Default")
      (node (ref "J2") (pin "10") (pinfunction "3.3_V_10") (pintype "passive+no_connect"))
    )
    (net (code "64") (name "unconnected-(J2-5_V-Pad08)") (class "Default")
      (node (ref "J2") (pin "08") (pinfunction "5_V_08") (pintype "passive+no_connect"))
    )
    (net (code "65") (name "unconnected-(J2-A-ADCS-Pad39)") (class "Default")
      (node (ref "J2") (pin "39") (pinfunction "A-ADCS_39") (pintype "passive+no_connect"))
    )
    (net (code "66") (name "unconnected-(J2-A-CAM-Pad25)") (class "Default")
      (node (ref "J2") (pin "25") (pinfunction "A-CAM_25") (pintype "passive+no_connect"))
    )
    (net (code "67") (name "unconnected-(J2-A-EPS-Pad01)") (class "Default")
      (node (ref "J2") (pin "01") (pinfunction "A-EPS_01") (pintype "passive+no_connect"))
    )
    (net (code "68") (name "unconnected-(J2-ADCS(5V-Pad22)") (class "Default")
      (node (ref "J2") (pin "22") (pinfunction "ADCS(5V_22") (pintype "passive+no_connect"))
    )
    (net (code "69") (name "unconnected-(J2-ADCS-MT(3.3V)-Pad20)") (class "Default")
      (node (ref "J2") (pin "20") (pinfunction "ADCS-MT(3.3V)_20") (pintype "passive+no_connect"))
    )
    (net (code "70") (name "unconnected-(J2-B-ADCS-Pad40)") (class "Default")
      (node (ref "J2") (pin "40") (pinfunction "B-ADCS_40") (pintype "passive+no_connect"))
    )
    (net (code "71") (name "unconnected-(J2-B-CAM-Pad27)") (class "Default")
      (node (ref "J2") (pin "27") (pinfunction "B-CAM_27") (pintype "passive+no_connect"))
    )
    (net (code "72") (name "unconnected-(J2-B-EPS-Pad02)") (class "Default")
      (node (ref "J2") (pin "02") (pinfunction "B-EPS_02") (pintype "passive+no_connect"))
    )
    (net (code "73") (name "unconnected-(J2-CAMERA_(5V)-Pad28)") (class "Default")
      (node (ref "J2") (pin "28") (pinfunction "CAMERA_(5V)_28") (pintype "passive+no_connect"))
    )
    (net (code "74") (name "unconnected-(J2-Exp(5_V)-Pad26)") (class "Default")
      (node (ref "J2") (pin "26") (pinfunction "Exp(5_V)_26") (pintype "passive+no_connect"))
    )
    (net (code "75") (name "unconnected-(J2-GND-Pad16)") (class "Default")
      (node (ref "J2") (pin "16") (pinfunction "GND_16") (pintype "passive+no_connect"))
    )
    (net (code "76") (name "unconnected-(J2-HRes_CS-Pad51)") (class "Default")
      (node (ref "J2") (pin "51") (pinfunction "HRes_CS_51") (pintype "passive+no_connect"))
    )
    (net (code "77") (name "unconnected-(J2-OBC_(3.3V)-Pad18)") (class "Default")
      (node (ref "J2") (pin "18") (pinfunction "OBC_(3.3V)_18") (pintype "passive+no_connect"))
    )
    (net (code "78") (name "unconnected-(J2-Pad07)") (class "Default")
      (node (ref "J2") (pin "07") (pinfunction "07_07") (pintype "passive+no_connect"))
    )
    (net (code "79") (name "unconnected-(J2-Pad09)") (class "Default")
      (node (ref "J2") (pin "09") (pinfunction "09_09") (pintype "passive+no_connect"))
    )
    (net (code "80") (name "unconnected-(J2-Pad15)") (class "Default")
      (node (ref "J2") (pin "15") (pinfunction "15_15") (pintype "passive+no_connect"))
    )
    (net (code "81") (name "unconnected-(J2-Pad21)") (class "Default")
      (node (ref "J2") (pin "21") (pinfunction "21_21") (pintype "passive+no_connect"))
    )
    (net (code "82") (name "unconnected-(J2-Pad23)") (class "Default")
      (node (ref "J2") (pin "23") (pinfunction "23_23") (pintype "passive+no_connect"))
    )
    (net (code "83") (name "unconnected-(J2-Pad33)") (class "Default")
      (node (ref "J2") (pin "33") (pinfunction "33_33") (pintype "passive+no_connect"))
    )
    (net (code "84") (name "unconnected-(J2-Pad34)") (class "Default")
      (node (ref "J2") (pin "34") (pinfunction "34_34") (pintype "passive+no_connect"))
    )
    (net (code "85") (name "unconnected-(J2-Pad35)") (class "Default")
      (node (ref "J2") (pin "35") (pinfunction "35_35") (pintype "passive+no_connect"))
    )
    (net (code "86") (name "unconnected-(J2-Pad36)") (class "Default")
      (node (ref "J2") (pin "36") (pinfunction "36_36") (pintype "passive+no_connect"))
    )
    (net (code "87") (name "unconnected-(J2-Pad37)") (class "Default")
      (node (ref "J2") (pin "37") (pinfunction "37_37") (pintype "passive+no_connect"))
    )
    (net (code "88") (name "unconnected-(J2-Pad38)") (class "Default")
      (node (ref "J2") (pin "38") (pinfunction "38_38") (pintype "passive+no_connect"))
    )
    (net (code "89") (name "unconnected-(J2-Pad41)") (class "Default")
      (node (ref "J2") (pin "41") (pinfunction "41_41") (pintype "passive+no_connect"))
    )
    (net (code "90") (name "unconnected-(J2-Pad43)") (class "Default")
      (node (ref "J2") (pin "43") (pinfunction "43_43") (pintype "passive+no_connect"))
    )
    (net (code "91") (name "unconnected-(J2-Pad47)") (class "Default")
      (node (ref "J2") (pin "47") (pinfunction "47_47") (pintype "passive+no_connect"))
    )
    (net (code "92") (name "unconnected-(J2-Pad48)") (class "Default")
      (node (ref "J2") (pin "48") (pinfunction "48_48") (pintype "passive+no_connect"))
    )
    (net (code "93") (name "unconnected-(J2-Pad49)") (class "Default")
      (node (ref "J2") (pin "49") (pinfunction "49_49") (pintype "passive+no_connect"))
    )
    (net (code "94") (name "unconnected-(J2-V_bat-Pad17)") (class "Default")
      (node (ref "J2") (pin "17") (pinfunction "V_bat_17") (pintype "passive+no_connect"))
    )
    (net (code "95") (name "unconnected-(J2-Y-ADCS-Pad42)") (class "Default")
      (node (ref "J2") (pin "42") (pinfunction "Y-ADCS_42") (pintype "passive+no_connect"))
    )
    (net (code "96") (name "unconnected-(J2-Y-EPS-Pad03)") (class "Default")
      (node (ref "J2") (pin "03") (pinfunction "Y-EPS_03") (pintype "passive+no_connect"))
    )
    (net (code "97") (name "unconnected-(J2-Z-ADCS-Pad44)") (class "Default")
      (node (ref "J2") (pin "44") (pinfunction "Z-ADCS_44") (pintype "passive+no_connect"))
    )
    (net (code "98") (name "unconnected-(J2-Z-EPS-Pad04)") (class "Default")
      (node (ref "J2") (pin "04") (pinfunction "Z-EPS_04") (pintype "passive+no_connect"))
    )
    (net (code "99") (name "unconnected-(U1D-PA8-Pad67)") (class "Default")
      (node (ref "U1") (pin "67") (pinfunction "PA8_67") (pintype "passive+no_connect"))
    )
    (net (code "100") (name "unconnected-(U1D-PA9-Pad68)") (class "Default")
      (node (ref "U1") (pin "68") (pinfunction "PA9_68") (pintype "passive+no_connect"))
    )
    (net (code "101") (name "unconnected-(U1D-PA10-Pad69)") (class "Default")
      (node (ref "U1") (pin "69") (pinfunction "PA10_69") (pintype "passive+no_connect"))
    )
    (net (code "102") (name "unconnected-(U1D-PA11-Pad70)") (class "Default")
      (node (ref "U1") (pin "70") (pinfunction "PA11_70") (pintype "passive+no_connect"))
    )
    (net (code "103") (name "unconnected-(U1D-PA12-Pad71)") (class "Default")
      (node (ref "U1") (pin "71") (pinfunction "PA12_71") (pintype "passive+no_connect"))
    )
    (net (code "104") (name "unconnected-(U1D-PB0-Pad35)") (class "Default")
      (node (ref "U1") (pin "35") (pinfunction "PB0_35") (pintype "passive+no_connect"))
    )
    (net (code "105") (name "unconnected-(U1D-PB1-Pad36)") (class "Default")
      (node (ref "U1") (pin "36") (pinfunction "PB1_36") (pintype "passive+no_connect"))
    )
    (net (code "106") (name "unconnected-(U1D-PB5-Pad91)") (class "Default")
      (node (ref "U1") (pin "91") (pinfunction "PB5_91") (pintype "passive+no_connect"))
    )
    (net (code "107") (name "unconnected-(U1D-PB6-Pad92)") (class "Default")
      (node (ref "U1") (pin "92") (pinfunction "PB6_92") (pintype "passive+no_connect"))
    )
    (net (code "108") (name "unconnected-(U1D-PB7-Pad93)") (class "Default")
      (node (ref "U1") (pin "93") (pinfunction "PB7_93") (pintype "passive+no_connect"))
    )
    (net (code "109") (name "unconnected-(U1D-PB8-Pad95)") (class "Default")
      (node (ref "U1") (pin "95") (pinfunction "PB8_95") (pintype "passive+no_connect"))
    )
    (net (code "110") (name "unconnected-(U1D-PB9-Pad96)") (class "Default")
      (node (ref "U1") (pin "96") (pinfunction "PB9_96") (pintype "passive+no_connect"))
    )
    (net (code "111") (name "unconnected-(U1D-PB10-Pad47)") (class "Default")
      (node (ref "U1") (pin "47") (pinfunction "PB10_47") (pintype "passive+no_connect"))
    )
    (net (code "112") (name "unconnected-(U1D-PB11-Pad48)") (class "Default")
      (node (ref "U1") (pin "48") (pinfunction "PB11_48") (pintype "passive+no_connect"))
    )
    (net (code "113") (name "unconnected-(U1D-PB12-Pad51)") (class "Default")
      (node (ref "U1") (pin "51") (pinfunction "PB12_51") (pintype "passive+no_connect"))
    )
    (net (code "114") (name "unconnected-(U1D-PB13-Pad52)") (class "Default")
      (node (ref "U1") (pin "52") (pinfunction "PB13_52") (pintype "passive+no_connect"))
    )
    (net (code "115") (name "unconnected-(U1D-PB14-Pad53)") (class "Default")
      (node (ref "U1") (pin "53") (pinfunction "PB14_53") (pintype "passive+no_connect"))
    )
    (net (code "116") (name "unconnected-(U1D-PB15-Pad54)") (class "Default")
      (node (ref "U1") (pin "54") (pinfunction "PB15_54") (pintype "passive+no_connect"))
    )
    (net (code "117") (name "unconnected-(U1D-PC0-Pad15)") (class "Default")
      (node (ref "U1") (pin "15") (pinfunction "PC0_15") (pintype "passive+no_connect"))
    )
    (net (code "118") (name "unconnected-(U1D-PC1-Pad16)") (class "Default")
      (node (ref "U1") (pin "16") (pinfunction "PC1_16") (pintype "passive+no_connect"))
    )
    (net (code "119") (name "unconnected-(U1D-PC3-Pad18)") (class "Default")
      (node (ref "U1") (pin "18") (pinfunction "PC3_18") (pintype "passive+no_connect"))
    )
    (net (code "120") (name "unconnected-(U1D-PC4-Pad33)") (class "Default")
      (node (ref "U1") (pin "33") (pinfunction "PC4_33") (pintype "passive+no_connect"))
    )
    (net (code "121") (name "unconnected-(U1D-PC5-Pad34)") (class "Default")
      (node (ref "U1") (pin "34") (pinfunction "PC5_34") (pintype "passive+no_connect"))
    )
    (net (code "122") (name "unconnected-(U1D-PC6-Pad63)") (class "Default")
      (node (ref "U1") (pin "63") (pinfunction "PC6_63") (pintype "passive+no_connect"))
    )
    (net (code "123") (name "unconnected-(U1D-PC7-Pad64)") (class "Default")
      (node (ref "U1") (pin "64") (pinfunction "PC7_64") (pintype "passive+no_connect"))
    )
    (net (code "124") (name "unconnected-(U1D-PC8-Pad65)") (class "Default")
      (node (ref "U1") (pin "65") (pinfunction "PC8_65") (pintype "passive+no_connect"))
    )
    (net (code "125") (name "unconnected-(U1D-PC9-Pad66)") (class "Default")
      (node (ref "U1") (pin "66") (pinfunction "PC9_66") (pintype "passive+no_connect"))
    )
    (net (code "126") (name "unconnected-(U1D-PC13-Pad7)") (class "Default")
      (node (ref "U1") (pin "7") (pinfunction "PC13_7") (pintype "passive+no_connect"))
    )
    (net (code "127") (name "unconnected-(U1D-PD0-Pad81)") (class "Default")
      (node (ref "U1") (pin "81") (pinfunction "PD0_81") (pintype "passive+no_connect"))
    )
    (net (code "128") (name "unconnected-(U1D-PD1-Pad82)") (class "Default")
      (node (ref "U1") (pin "82") (pinfunction "PD1_82") (pintype "passive+no_connect"))
    )
    (net (code "129") (name "unconnected-(U1D-PD3-Pad84)") (class "Default")
      (node (ref "U1") (pin "84") (pinfunction "PD3_84") (pintype "passive+no_connect"))
    )
    (net (code "130") (name "unconnected-(U1D-PD4-Pad85)") (class "Default")
      (node (ref "U1") (pin "85") (pinfunction "PD4_85") (pintype "passive+no_connect"))
    )
    (net (code "131") (name "unconnected-(U1D-PD5-Pad86)") (class "Default")
      (node (ref "U1") (pin "86") (pinfunction "PD5_86") (pintype "passive+no_connect"))
    )
    (net (code "132") (name "unconnected-(U1D-PD6-Pad87)") (class "Default")
      (node (ref "U1") (pin "87") (pinfunction "PD6_87") (pintype "passive+no_connect"))
    )
    (net (code "133") (name "unconnected-(U1D-PD7-Pad88)") (class "Default")
      (node (ref "U1") (pin "88") (pinfunction "PD7_88") (pintype "passive+no_connect"))
    )
    (net (code "134") (name "unconnected-(U1D-PD8-Pad55)") (class "Default")
      (node (ref "U1") (pin "55") (pinfunction "PD8_55") (pintype "passive+no_connect"))
    )
    (net (code "135") (name "unconnected-(U1D-PD9-Pad56)") (class "Default")
      (node (ref "U1") (pin "56") (pinfunction "PD9_56") (pintype "passive+no_connect"))
    )
    (net (code "136") (name "unconnected-(U1D-PD10-Pad57)") (class "Default")
      (node (ref "U1") (pin "57") (pinfunction "PD10_57") (pintype "passive+no_connect"))
    )
    (net (code "137") (name "unconnected-(U1D-PD11-Pad58)") (class "Default")
      (node (ref "U1") (pin "58") (pinfunction "PD11_58") (pintype "passive+no_connect"))
    )
    (net (code "138") (name "unconnected-(U1D-PE0-Pad97)") (class "Default")
      (node (ref "U1") (pin "97") (pinfunction "PE0_97") (pintype "passive+no_connect"))
    )
    (net (code "139") (name "unconnected-(U1D-PE1-Pad98)") (class "Default")
      (node (ref "U1") (pin "98") (pinfunction "PE1_98") (pintype "passive+no_connect"))
    )
    (net (code "140") (name "unconnected-(U1D-PE4-Pad3)") (class "Default")
      (node (ref "U1") (pin "3") (pinfunction "PE4_3") (pintype "passive+no_connect"))
    )
    (net (code "141") (name "unconnected-(U1D-PE5-Pad4)") (class "Default")
      (node (ref "U1") (pin "4") (pinfunction "PE5_4") (pintype "passive+no_connect"))
    )
    (net (code "142") (name "unconnected-(U1D-PE6-Pad5)") (class "Default")
      (node (ref "U1") (pin "5") (pinfunction "PE6_5") (pintype "passive+no_connect"))
    )
    (net (code "143") (name "unconnected-(U1D-PE8-Pad39)") (class "Default")
      (node (ref "U1") (pin "39") (pinfunction "PE8_39") (pintype "passive+no_connect"))
    )
    (net (code "144") (name "unconnected-(U1D-PE9-Pad40)") (class "Default")
      (node (ref "U1") (pin "40") (pinfunction "PE9_40") (pintype "passive+no_connect"))
    )
    (net (code "145") (name "unconnected-(U1D-PE10-Pad41)") (class "Default")
      (node (ref "U1") (pin "41") (pinfunction "PE10_41") (pintype "passive+no_connect"))
    )
    (net (code "146") (name "unconnected-(U1D-PE11-Pad42)") (class "Default")
      (node (ref "U1") (pin "42") (pinfunction "PE11_42") (pintype "passive+no_connect"))
    )
    (net (code "147") (name "unconnected-(U1D-PE12-Pad43)") (class "Default")
      (node (ref "U1") (pin "43") (pinfunction "PE12_43") (pintype "passive+no_connect"))
    )
    (net (code "148") (name "unconnected-(U1D-PE13-Pad44)") (class "Default")
      (node (ref "U1") (pin "44") (pinfunction "PE13_44") (pintype "passive+no_connect"))
    )
    (net (code "149") (name "unconnected-(U1D-PE14-Pad45)") (class "Default")
      (node (ref "U1") (pin "45") (pinfunction "PE14_45") (pintype "passive+no_connect"))
    )
    (net (code "150") (name "unconnected-(U1D-PE15-Pad46)") (class "Default")
      (node (ref "U1") (pin "46") (pinfunction "PE15_46") (pintype "passive+no_connect"))
    )
    (net (code "151") (name "unconnected-(X1-GND-Pad2)") (class "Default")
      (node (ref "X1") (pin "2") (pinfunction "GND_2") (pintype "passive+no_connect"))
    )
    (net (code "152") (name "unconnected-(X1-GND-Pad3)") (class "Default")
      (node (ref "X1") (pin "3") (pinfunction "GND_3") (pintype "passive+no_connect"))
    )
  )
)
